# IO_Top_BOARD.net
KiCad netlist of a schematic drawn in EAGLE
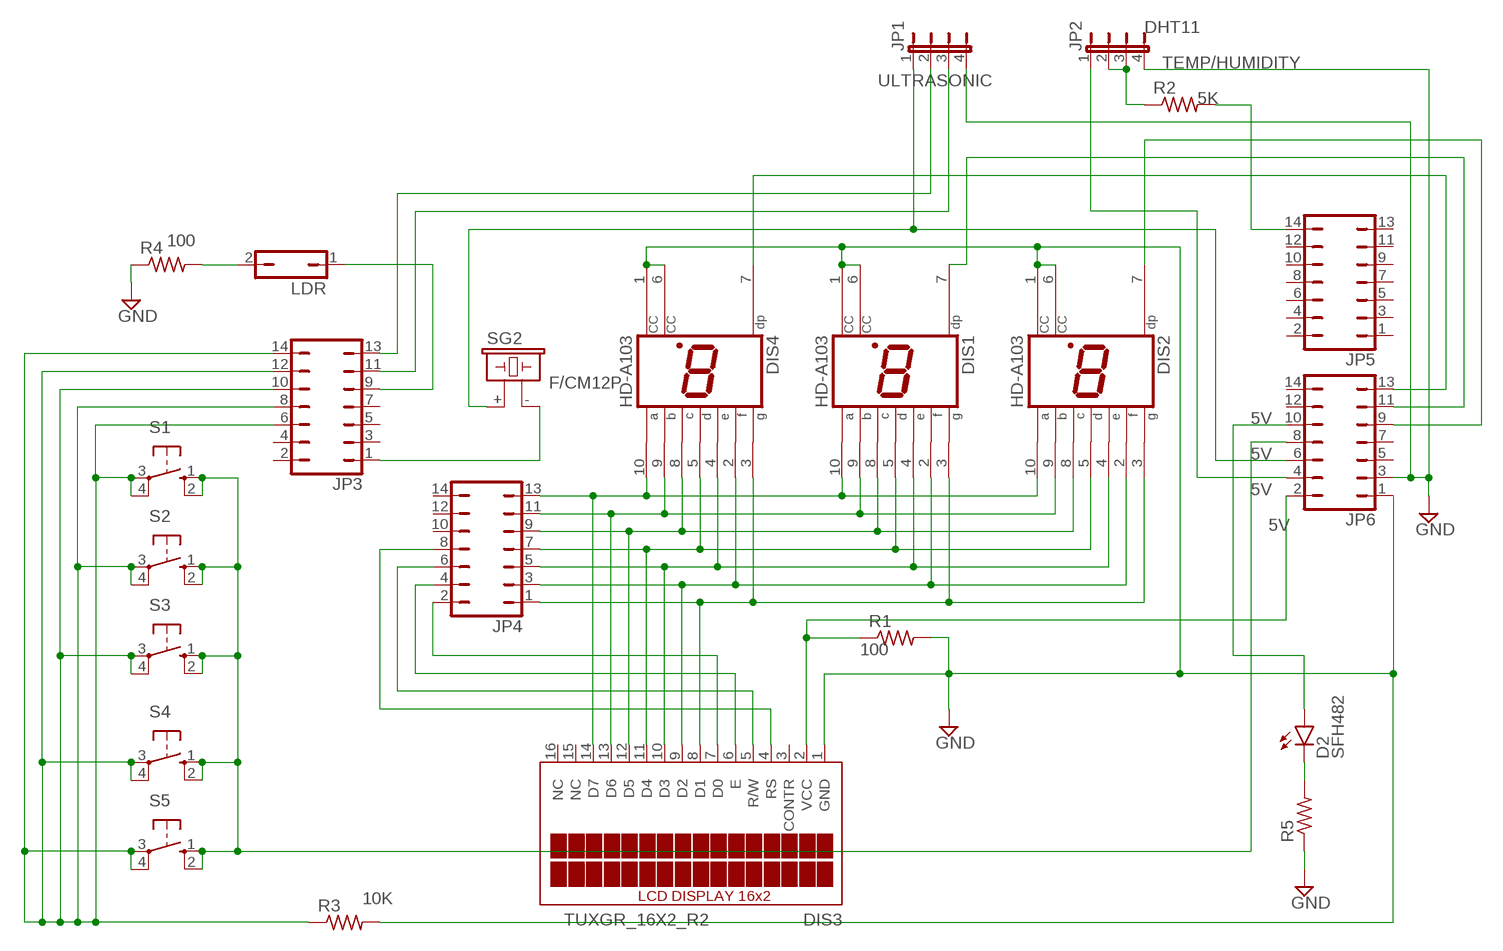
[diagram p0: schematic, sheet 1]

(export (version "E")
  (design (tool "Eeschema 10.0.6"))
  (components
    (comp (ref "D2")
      (value "SFH482")
      (footprint "eagle-import:SFH482")
      (libsource (lib "eagle-import") (part "SFH482"))
    )
    (comp (ref "DIS1")
      (value "HD-A103")
      (footprint "eagle-import:HDSP-A")
      (libsource (lib "eagle-import") (part "HD-A103"))
    )
    (comp (ref "DIS2")
      (value "HD-A103")
      (footprint "eagle-import:HDSP-A")
      (libsource (lib "eagle-import") (part "HD-A103"))
    )
    (comp (ref "DIS3")
      (value "TUXGR_16X2_R2")
      (footprint "eagle-import:TUXGR_16X2_R2")
      (libsource (lib "eagle-import") (part "TUXGR_16X2_R2"))
    )
    (comp (ref "DIS4")
      (value "HD-A103")
      (footprint "eagle-import:HDSP-A")
      (libsource (lib "eagle-import") (part "HD-A103"))
    )
    (comp (ref "JP1")
      (value "JP4E")
      (footprint "eagle-import:JP4")
      (libsource (lib "eagle-import") (part "JP4E"))
    )
    (comp (ref "JP2")
      (value "JP4E")
      (footprint "eagle-import:JP4")
      (libsource (lib "eagle-import") (part "JP4E"))
    )
    (comp (ref "JP3")
      (value "JP7Q")
      (footprint "eagle-import:JP7Q")
      (libsource (lib "eagle-import") (part "JP7Q"))
    )
    (comp (ref "JP4")
      (value "JP7Q")
      (footprint "eagle-import:JP7Q")
      (libsource (lib "eagle-import") (part "JP7Q"))
    )
    (comp (ref "JP5")
      (value "JP7Q")
      (footprint "eagle-import:JP7Q")
      (libsource (lib "eagle-import") (part "JP7Q"))
    )
    (comp (ref "JP6")
      (value "JP7Q")
      (footprint "eagle-import:JP7Q")
      (libsource (lib "eagle-import") (part "JP7Q"))
    )
    (comp (ref "LDR")
      (value "JP1Q")
      (footprint "eagle-import:JP1")
      (libsource (lib "eagle-import") (part "JP1Q"))
    )
    (comp (ref "R1")
      (value "R-US_0204/2V")
      (footprint "eagle-import:0204V")
      (libsource (lib "eagle-import") (part "R-US_0204/2V"))
    )
    (comp (ref "R2")
      (value "R-US_0204/2V")
      (footprint "eagle-import:0204V")
      (libsource (lib "eagle-import") (part "R-US_0204/2V"))
    )
    (comp (ref "R3")
      (value "R-US_0204/2V")
      (footprint "eagle-import:0204V")
      (libsource (lib "eagle-import") (part "R-US_0204/2V"))
    )
    (comp (ref "R4")
      (value "R-US_0204/2V")
      (footprint "eagle-import:0204V")
      (libsource (lib "eagle-import") (part "R-US_0204/2V"))
    )
    (comp (ref "R5")
      (value "R-US_0204/2V")
      (footprint "eagle-import:0204V")
      (libsource (lib "eagle-import") (part "R-US_0204/2V"))
    )
    (comp (ref "S1")
      (value "10-XX")
      (footprint "eagle-import:B3F-10XX")
      (fields (field (name "MPN") "B3F-1000"))
      (libsource (lib "eagle-import") (part "10-XX"))
    )
    (comp (ref "S2")
      (value "10-XX")
      (footprint "eagle-import:B3F-10XX")
      (fields (field (name "MPN") "B3F-1000"))
      (libsource (lib "eagle-import") (part "10-XX"))
    )
    (comp (ref "S3")
      (value "10-XX")
      (footprint "eagle-import:B3F-10XX")
      (fields (field (name "MPN") "B3F-1000"))
      (libsource (lib "eagle-import") (part "10-XX"))
    )
    (comp (ref "S4")
      (value "10-XX")
      (footprint "eagle-import:B3F-10XX")
      (fields (field (name "MPN") "B3F-1000"))
      (libsource (lib "eagle-import") (part "10-XX"))
    )
    (comp (ref "S5")
      (value "10-XX")
      (footprint "eagle-import:B3F-10XX")
      (fields (field (name "MPN") "B3F-1000"))
      (libsource (lib "eagle-import") (part "10-XX"))
    )
    (comp (ref "SG2")
      (value "F/CM12P")
      (footprint "eagle-import:F_CM12P")
      (libsource (lib "eagle-import") (part "F/CM12P"))
    )
  )
  (nets
    (net (code "1") (name "/5V") (class "Default")
      (node (ref "JP1") (pin "1") (pinfunction "1_1") (pintype "passive"))
      (node (ref "JP6") (pin "6") (pinfunction "6_6") (pintype "passive"))
      (node (ref "SG2") (pin "+") (pinfunction "1_+") (pintype "passive"))
    )
    (net (code "2") (name "GND") (class "Default")
      (node (ref "DIS1") (pin "1") (pinfunction "CC_1") (pintype "passive"))
      (node (ref "DIS1") (pin "6") (pinfunction "CC_6") (pintype "passive"))
      (node (ref "DIS2") (pin "1") (pinfunction "CC_1") (pintype "passive"))
      (node (ref "DIS2") (pin "6") (pinfunction "CC_6") (pintype "passive"))
      (node (ref "DIS3") (pin "1") (pinfunction "GND_1") (pintype "power_in"))
      (node (ref "DIS4") (pin "1") (pinfunction "CC_1") (pintype "passive"))
      (node (ref "DIS4") (pin "6") (pinfunction "CC_6") (pintype "passive"))
      (node (ref "JP1") (pin "4") (pinfunction "4_4") (pintype "passive"))
      (node (ref "JP2") (pin "4") (pinfunction "4_4") (pintype "passive"))
      (node (ref "JP6") (pin "1") (pinfunction "1_1") (pintype "passive"))
      (node (ref "JP6") (pin "3") (pinfunction "3_3") (pintype "passive"))
      (node (ref "R1") (pin "2") (pinfunction "2_2") (pintype "passive"))
      (node (ref "R3") (pin "2") (pinfunction "2_2") (pintype "passive"))
      (node (ref "R4") (pin "1") (pinfunction "1_1") (pintype "passive"))
      (node (ref "R5") (pin "1") (pinfunction "1_1") (pintype "passive"))
    )
    (net (code "3") (name "Net-(D2-C)") (class "Default")
      (node (ref "D2") (pin "K") (pinfunction "C_K") (pintype "passive"))
      (node (ref "R5") (pin "2") (pinfunction "2_2") (pintype "passive"))
    )
    (net (code "4") (name "Net-(D2-PadA)") (class "Default")
      (node (ref "D2") (pin "A") (pinfunction "A_A") (pintype "passive"))
      (node (ref "JP6") (pin "10") (pinfunction "10_10") (pintype "passive"))
    )
    (net (code "5") (name "Net-(DIS1-A)") (class "Default")
      (node (ref "DIS1") (pin "10") (pinfunction "A_10") (pintype "passive"))
      (node (ref "DIS2") (pin "10") (pinfunction "A_10") (pintype "passive"))
      (node (ref "DIS3") (pin "14") (pinfunction "D7_14") (pintype "input"))
      (node (ref "DIS4") (pin "10") (pinfunction "A_10") (pintype "passive"))
      (node (ref "JP4") (pin "13") (pinfunction "13_13") (pintype "passive"))
    )
    (net (code "6") (name "Net-(DIS1-B)") (class "Default")
      (node (ref "DIS1") (pin "9") (pinfunction "B_9") (pintype "passive"))
      (node (ref "DIS2") (pin "9") (pinfunction "B_9") (pintype "passive"))
      (node (ref "DIS3") (pin "13") (pinfunction "D6_13") (pintype "input"))
      (node (ref "DIS4") (pin "9") (pinfunction "B_9") (pintype "passive"))
      (node (ref "JP4") (pin "11") (pinfunction "11_11") (pintype "passive"))
    )
    (net (code "7") (name "Net-(DIS1-C)") (class "Default")
      (node (ref "DIS1") (pin "8") (pinfunction "C_8") (pintype "passive"))
      (node (ref "DIS2") (pin "8") (pinfunction "C_8") (pintype "passive"))
      (node (ref "DIS3") (pin "12") (pinfunction "D5_12") (pintype "input"))
      (node (ref "DIS4") (pin "8") (pinfunction "C_8") (pintype "passive"))
      (node (ref "JP4") (pin "9") (pinfunction "9_9") (pintype "passive"))
    )
    (net (code "8") (name "Net-(DIS1-D)") (class "Default")
      (node (ref "DIS1") (pin "5") (pinfunction "D_5") (pintype "passive"))
      (node (ref "DIS2") (pin "5") (pinfunction "D_5") (pintype "passive"))
      (node (ref "DIS3") (pin "11") (pinfunction "D4_11") (pintype "input"))
      (node (ref "DIS4") (pin "5") (pinfunction "D_5") (pintype "passive"))
      (node (ref "JP4") (pin "7") (pinfunction "7_7") (pintype "passive"))
    )
    (net (code "9") (name "Net-(DIS1-DP)") (class "Default")
      (node (ref "DIS1") (pin "7") (pinfunction "DP_7") (pintype "passive"))
      (node (ref "JP6") (pin "11") (pinfunction "11_11") (pintype "passive"))
    )
    (net (code "10") (name "Net-(DIS1-E)") (class "Default")
      (node (ref "DIS1") (pin "4") (pinfunction "E_4") (pintype "passive"))
      (node (ref "DIS2") (pin "4") (pinfunction "E_4") (pintype "passive"))
      (node (ref "DIS3") (pin "10") (pinfunction "D3_10") (pintype "input"))
      (node (ref "DIS4") (pin "4") (pinfunction "E_4") (pintype "passive"))
      (node (ref "JP4") (pin "5") (pinfunction "5_5") (pintype "passive"))
    )
    (net (code "11") (name "Net-(DIS1-F)") (class "Default")
      (node (ref "DIS1") (pin "2") (pinfunction "F_2") (pintype "passive"))
      (node (ref "DIS2") (pin "2") (pinfunction "F_2") (pintype "passive"))
      (node (ref "DIS3") (pin "9") (pinfunction "D2_9") (pintype "input"))
      (node (ref "DIS4") (pin "2") (pinfunction "F_2") (pintype "passive"))
      (node (ref "JP4") (pin "3") (pinfunction "3_3") (pintype "passive"))
    )
    (net (code "12") (name "Net-(DIS1-G)") (class "Default")
      (node (ref "DIS1") (pin "3") (pinfunction "G_3") (pintype "passive"))
      (node (ref "DIS2") (pin "3") (pinfunction "G_3") (pintype "passive"))
      (node (ref "DIS3") (pin "8") (pinfunction "D1_8") (pintype "input"))
      (node (ref "DIS4") (pin "3") (pinfunction "G_3") (pintype "passive"))
      (node (ref "JP4") (pin "1") (pinfunction "1_1") (pintype "passive"))
    )
    (net (code "13") (name "Net-(DIS2-DP)") (class "Default")
      (node (ref "DIS2") (pin "7") (pinfunction "DP_7") (pintype "passive"))
      (node (ref "JP6") (pin "9") (pinfunction "9_9") (pintype "passive"))
    )
    (net (code "14") (name "Net-(DIS3-D0)") (class "Default")
      (node (ref "DIS3") (pin "7") (pinfunction "D0_7") (pintype "input"))
      (node (ref "JP4") (pin "2") (pinfunction "2_2") (pintype "passive"))
    )
    (net (code "15") (name "Net-(DIS3-E)") (class "Default")
      (node (ref "DIS3") (pin "6") (pinfunction "E_6") (pintype "input"))
      (node (ref "JP4") (pin "4") (pinfunction "4_4") (pintype "passive"))
    )
    (net (code "16") (name "Net-(DIS3-RS)") (class "Default")
      (node (ref "DIS3") (pin "4") (pinfunction "RS_4") (pintype "input"))
      (node (ref "JP4") (pin "8") (pinfunction "8_8") (pintype "passive"))
    )
    (net (code "17") (name "Net-(DIS3-R{slash}W)") (class "Default")
      (node (ref "DIS3") (pin "5") (pinfunction "R/W_5") (pintype "input"))
      (node (ref "JP4") (pin "6") (pinfunction "6_6") (pintype "passive"))
    )
    (net (code "18") (name "Net-(DIS3-VCC)") (class "Default")
      (node (ref "DIS3") (pin "2") (pinfunction "VCC_2") (pintype "power_in"))
      (node (ref "JP6") (pin "2") (pinfunction "2_2") (pintype "passive"))
      (node (ref "R1") (pin "1") (pinfunction "1_1") (pintype "passive"))
    )
    (net (code "19") (name "Net-(DIS4-DP)") (class "Default")
      (node (ref "DIS4") (pin "7") (pinfunction "DP_7") (pintype "passive"))
      (node (ref "JP6") (pin "13") (pinfunction "13_13") (pintype "passive"))
    )
    (net (code "20") (name "Net-(JP1-Pad2)") (class "Default")
      (node (ref "JP1") (pin "2") (pinfunction "2_2") (pintype "passive"))
      (node (ref "JP3") (pin "13") (pinfunction "13_13") (pintype "passive"))
    )
    (net (code "21") (name "Net-(JP1-Pad3)") (class "Default")
      (node (ref "JP1") (pin "3") (pinfunction "3_3") (pintype "passive"))
      (node (ref "JP3") (pin "11") (pinfunction "11_11") (pintype "passive"))
    )
    (net (code "22") (name "Net-(JP2-Pad1)") (class "Default")
      (node (ref "JP2") (pin "1") (pinfunction "1_1") (pintype "passive"))
      (node (ref "JP6") (pin "4") (pinfunction "4_4") (pintype "passive"))
    )
    (net (code "23") (name "Net-(JP2-Pad2)") (class "Default")
      (node (ref "JP2") (pin "2") (pinfunction "2_2") (pintype "passive"))
      (node (ref "JP2") (pin "3") (pinfunction "3_3") (pintype "passive"))
      (node (ref "R2") (pin "1") (pinfunction "1_1") (pintype "passive"))
    )
    (net (code "24") (name "Net-(JP3-Pad9)") (class "Default")
      (node (ref "JP3") (pin "9") (pinfunction "9_9") (pintype "passive"))
      (node (ref "LDR") (pin "1") (pinfunction "1_1") (pintype "passive"))
    )
    (net (code "25") (name "Net-(JP5-Pad14)") (class "Default")
      (node (ref "JP5") (pin "14") (pinfunction "14_14") (pintype "passive"))
      (node (ref "R2") (pin "2") (pinfunction "2_2") (pintype "passive"))
    )
    (net (code "26") (name "Net-(LDR-Pad2)") (class "Default")
      (node (ref "LDR") (pin "2") (pinfunction "2_2") (pintype "passive"))
      (node (ref "R4") (pin "2") (pinfunction "2_2") (pintype "passive"))
    )
    (net (code "27") (name "Net-(S1-P)") (class "Default")
      (node (ref "JP3") (pin "10") (pinfunction "10_10") (pintype "passive"))
      (node (ref "JP3") (pin "12") (pinfunction "12_12") (pintype "passive"))
      (node (ref "JP3") (pin "14") (pinfunction "14_14") (pintype "passive"))
      (node (ref "JP3") (pin "6") (pinfunction "6_6") (pintype "passive"))
      (node (ref "JP3") (pin "8") (pinfunction "8_8") (pintype "passive"))
      (node (ref "R3") (pin "1") (pinfunction "1_1") (pintype "passive"))
      (node (ref "S1") (pin "3") (pinfunction "P_3") (pintype "passive"))
      (node (ref "S1") (pin "4") (pinfunction "P1_4") (pintype "passive"))
      (node (ref "S2") (pin "3") (pinfunction "P_3") (pintype "passive"))
      (node (ref "S2") (pin "4") (pinfunction "P1_4") (pintype "passive"))
      (node (ref "S3") (pin "3") (pinfunction "P_3") (pintype "passive"))
      (node (ref "S3") (pin "4") (pinfunction "P1_4") (pintype "passive"))
      (node (ref "S4") (pin "3") (pinfunction "P_3") (pintype "passive"))
      (node (ref "S4") (pin "4") (pinfunction "P1_4") (pintype "passive"))
      (node (ref "S5") (pin "3") (pinfunction "P_3") (pintype "passive"))
      (node (ref "S5") (pin "4") (pinfunction "P1_4") (pintype "passive"))
    )
    (net (code "28") (name "Net-(S1-S)") (class "Default")
      (node (ref "JP6") (pin "8") (pinfunction "8_8") (pintype "passive"))
      (node (ref "S1") (pin "1") (pinfunction "S_1") (pintype "passive"))
      (node (ref "S1") (pin "2") (pinfunction "S1_2") (pintype "passive"))
      (node (ref "S2") (pin "1") (pinfunction "S_1") (pintype "passive"))
      (node (ref "S2") (pin "2") (pinfunction "S1_2") (pintype "passive"))
      (node (ref "S3") (pin "1") (pinfunction "S_1") (pintype "passive"))
      (node (ref "S3") (pin "2") (pinfunction "S1_2") (pintype "passive"))
      (node (ref "S4") (pin "1") (pinfunction "S_1") (pintype "passive"))
      (node (ref "S4") (pin "2") (pinfunction "S1_2") (pintype "passive"))
      (node (ref "S5") (pin "1") (pinfunction "S_1") (pintype "passive"))
      (node (ref "S5") (pin "2") (pinfunction "S1_2") (pintype "passive"))
    )
    (net (code "29") (name "Net-(SG2-2)") (class "Default")
      (node (ref "JP3") (pin "1") (pinfunction "1_1") (pintype "passive"))
      (node (ref "SG2") (pin "-") (pinfunction "2_-") (pintype "passive"))
    )
    (net (code "30") (name "unconnected-(DIS3-CONTR-Pad3)") (class "Default")
      (node (ref "DIS3") (pin "3") (pinfunction "CONTR_3") (pintype "input"))
    )
    (net (code "31") (name "unconnected-(DIS3-NC-Pad15)") (class "Default")
      (node (ref "DIS3") (pin "15") (pinfunction "NC_15") (pintype "no_connect"))
    )
    (net (code "32") (name "unconnected-(DIS3-NC-Pad16)") (class "Default")
      (node (ref "DIS3") (pin "16") (pinfunction "NC_16") (pintype "no_connect"))
    )
    (net (code "33") (name "unconnected-(JP3-Pad2)") (class "Default")
      (node (ref "JP3") (pin "2") (pinfunction "2_2") (pintype "passive"))
    )
    (net (code "34") (name "unconnected-(JP3-Pad3)") (class "Default")
      (node (ref "JP3") (pin "3") (pinfunction "3_3") (pintype "passive"))
    )
    (net (code "35") (name "unconnected-(JP3-Pad4)") (class "Default")
      (node (ref "JP3") (pin "4") (pinfunction "4_4") (pintype "passive"))
    )
    (net (code "36") (name "unconnected-(JP3-Pad5)") (class "Default")
      (node (ref "JP3") (pin "5") (pinfunction "5_5") (pintype "passive"))
    )
    (net (code "37") (name "unconnected-(JP3-Pad7)") (class "Default")
      (node (ref "JP3") (pin "7") (pinfunction "7_7") (pintype "passive"))
    )
    (net (code "38") (name "unconnected-(JP4-Pad10)") (class "Default")
      (node (ref "JP4") (pin "10") (pinfunction "10_10") (pintype "passive"))
    )
    (net (code "39") (name "unconnected-(JP4-Pad12)") (class "Default")
      (node (ref "JP4") (pin "12") (pinfunction "12_12") (pintype "passive"))
    )
    (net (code "40") (name "unconnected-(JP4-Pad14)") (class "Default")
      (node (ref "JP4") (pin "14") (pinfunction "14_14") (pintype "passive"))
    )
    (net (code "41") (name "unconnected-(JP5-Pad1)") (class "Default")
      (node (ref "JP5") (pin "1") (pinfunction "1_1") (pintype "passive"))
    )
    (net (code "42") (name "unconnected-(JP5-Pad2)") (class "Default")
      (node (ref "JP5") (pin "2") (pinfunction "2_2") (pintype "passive"))
    )
    (net (code "43") (name "unconnected-(JP5-Pad3)") (class "Default")
      (node (ref "JP5") (pin "3") (pinfunction "3_3") (pintype "passive"))
    )
    (net (code "44") (name "unconnected-(JP5-Pad4)") (class "Default")
      (node (ref "JP5") (pin "4") (pinfunction "4_4") (pintype "passive"))
    )
    (net (code "45") (name "unconnected-(JP5-Pad5)") (class "Default")
      (node (ref "JP5") (pin "5") (pinfunction "5_5") (pintype "passive"))
    )
    (net (code "46") (name "unconnected-(JP5-Pad6)") (class "Default")
      (node (ref "JP5") (pin "6") (pinfunction "6_6") (pintype "passive"))
    )
    (net (code "47") (name "unconnected-(JP5-Pad7)") (class "Default")
      (node (ref "JP5") (pin "7") (pinfunction "7_7") (pintype "passive"))
    )
    (net (code "48") (name "unconnected-(JP5-Pad8)") (class "Default")
      (node (ref "JP5") (pin "8") (pinfunction "8_8") (pintype "passive"))
    )
    (net (code "49") (name "unconnected-(JP5-Pad9)") (class "Default")
      (node (ref "JP5") (pin "9") (pinfunction "9_9") (pintype "passive"))
    )
    (net (code "50") (name "unconnected-(JP5-Pad10)") (class "Default")
      (node (ref "JP5") (pin "10") (pinfunction "10_10") (pintype "passive"))
    )
    (net (code "51") (name "unconnected-(JP5-Pad11)") (class "Default")
      (node (ref "JP5") (pin "11") (pinfunction "11_11") (pintype "passive"))
    )
    (net (code "52") (name "unconnected-(JP5-Pad12)") (class "Default")
      (node (ref "JP5") (pin "12") (pinfunction "12_12") (pintype "passive"))
    )
    (net (code "53") (name "unconnected-(JP5-Pad13)") (class "Default")
      (node (ref "JP5") (pin "13") (pinfunction "13_13") (pintype "passive"))
    )
    (net (code "54") (name "unconnected-(JP6-Pad5)") (class "Default")
      (node (ref "JP6") (pin "5") (pinfunction "5_5") (pintype "passive"))
    )
    (net (code "55") (name "unconnected-(JP6-Pad7)") (class "Default")
      (node (ref "JP6") (pin "7") (pinfunction "7_7") (pintype "passive"))
    )
    (net (code "56") (name "unconnected-(JP6-Pad12)") (class "Default")
      (node (ref "JP6") (pin "12") (pinfunction "12_12") (pintype "passive"))
    )
    (net (code "57") (name "unconnected-(JP6-Pad14)") (class "Default")
      (node (ref "JP6") (pin "14") (pinfunction "14_14") (pintype "passive"))
    )
  )
)
